# ESP_programmer_QFN.net
KiCad netlist of a schematic drawn in EAGLE
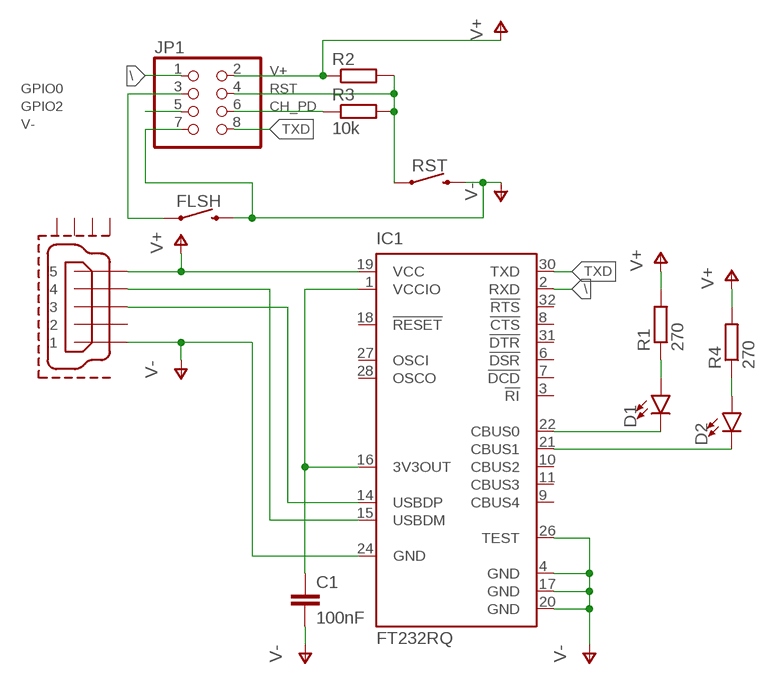
[diagram p0: schematic, sheet 1]

(export (version "E")
  (design (tool "Eeschema 10.0.6"))
  (components
    (comp (ref "C1")
      (value "100nF")
      (footprint "eagle-import:0603")
      (libsource (lib "eagle-import") (part "0.22UF-0603-25V-10%"))
    )
    (comp (ref "D1")
      (value "TX")
      (footprint "eagle-import:LED-0603")
      (libsource (lib "eagle-import") (part "LED-BLUE0603"))
    )
    (comp (ref "D2")
      (value "RX")
      (footprint "eagle-import:LED-0603")
      (libsource (lib "eagle-import") (part "LED-BLUE0603"))
    )
    (comp (ref "FLSH")
      (value "MOMENTARY-SWITCH-SPST-SMD-5.2-REDUNDANT")
      (footprint "eagle-import:TACTILE_SWITCH_SMD_5.2MM")
      (libsource (lib "eagle-import") (part "MOMENTARY-SWITCH-SPST-SMD-5.2-REDUNDANT"))
    )
    (comp (ref "IC1")
      (value "FT232RQ")
      (footprint "eagle-import:QFN32")
      (libsource (lib "eagle-import") (part "FT232RQ"))
    )
    (comp (ref "JP1")
      (value "PINHD-2X4")
      (footprint "eagle-import:2X04")
      (libsource (lib "eagle-import") (part "PINHD-2X4"))
    )
    (comp (ref "R1")
      (value "270")
      (footprint "eagle-import:MINI_MELF-0102R")
      (libsource (lib "eagle-import") (part "R-EU_MELF0102R"))
    )
    (comp (ref "R2")
      (value "10k")
      (footprint "eagle-import:MINI_MELF-0102R")
      (libsource (lib "eagle-import") (part "R-EU_MELF0102R"))
    )
    (comp (ref "R3")
      (value "10k")
      (footprint "eagle-import:MINI_MELF-0102R")
      (libsource (lib "eagle-import") (part "R-EU_MELF0102R"))
    )
    (comp (ref "R4")
      (value "270")
      (footprint "eagle-import:MINI_MELF-0102R")
      (libsource (lib "eagle-import") (part "R-EU_MELF0102R"))
    )
    (comp (ref "RST")
      (value "MOMENTARY-SWITCH-SPST-SMD-5.2-REDUNDANT")
      (footprint "eagle-import:TACTILE_SWITCH_SMD_5.2MM")
      (libsource (lib "eagle-import") (part "MOMENTARY-SWITCH-SPST-SMD-5.2-REDUNDANT"))
    )
    (comp (ref "U1")
      (value "MICRO-USB-RECEPTACLE47589-0001")
      (footprint "eagle-import:47589-0001")
      (libsource (lib "eagle-import") (part "MICRO-USB-RECEPTACLE47589-0001"))
    )
  )
  (nets
    (net (code "1") (name "/CH_PD") (class "Default")
      (node (ref "JP1") (pin "6") (pinfunction "6_6") (pintype "passive"))
      (node (ref "R3") (pin "1") (pinfunction "1_1") (pintype "passive"))
    )
    (net (code "2") (name "/GPIO0") (class "Default")
      (node (ref "FLSH") (pin "1") (pinfunction "1_1") (pintype "passive"))
      (node (ref "FLSH") (pin "2") (pinfunction "1_2") (pintype "passive"))
      (node (ref "JP1") (pin "3") (pinfunction "3_3") (pintype "passive"))
    )
    (net (code "3") (name "/GPIO2") (class "Default")
      (node (ref "JP1") (pin "5") (pinfunction "5_5") (pintype "passive"))
    )
    (net (code "4") (name "/RST") (class "Default")
      (node (ref "JP1") (pin "4") (pinfunction "4_4") (pintype "passive"))
      (node (ref "R2") (pin "2") (pinfunction "2_2") (pintype "passive"))
      (node (ref "R3") (pin "2") (pinfunction "2_2") (pintype "passive"))
      (node (ref "RST") (pin "1") (pinfunction "1_1") (pintype "passive"))
      (node (ref "RST") (pin "2") (pinfunction "1_2") (pintype "passive"))
    )
    (net (code "5") (name "Net-(D1-PadA)") (class "Default")
      (node (ref "D1") (pin "A") (pinfunction "A_A") (pintype "passive"))
      (node (ref "R1") (pin "1") (pinfunction "1_1") (pintype "passive"))
    )
    (net (code "6") (name "Net-(D2-PadA)") (class "Default")
      (node (ref "D2") (pin "A") (pinfunction "A_A") (pintype "passive"))
      (node (ref "R4") (pin "1") (pinfunction "1_1") (pintype "passive"))
    )
    (net (code "7") (name "Net-(IC1-3V3OUT)") (class "Default")
      (node (ref "C1") (pin "1") (pinfunction "1_1") (pintype "passive"))
      (node (ref "IC1") (pin "1") (pinfunction "VCCIO_1") (pintype "power_in"))
      (node (ref "IC1") (pin "16") (pinfunction "3V3OUT_16") (pintype "output"))
    )
    (net (code "8") (name "Net-(IC1-CBUS0)") (class "Default")
      (node (ref "D1") (pin "C") (pinfunction "C_C") (pintype "passive"))
      (node (ref "IC1") (pin "22") (pinfunction "CBUS0_22") (pintype "bidirectional"))
    )
    (net (code "9") (name "Net-(IC1-CBUS1)") (class "Default")
      (node (ref "D2") (pin "C") (pinfunction "C_C") (pintype "passive"))
      (node (ref "IC1") (pin "21") (pinfunction "CBUS1_21") (pintype "bidirectional"))
    )
    (net (code "10") (name "Net-(IC1-USBDM)") (class "Default")
      (node (ref "IC1") (pin "15") (pinfunction "USBDM_15") (pintype "bidirectional"))
      (node (ref "U1") (pin "4") (pinfunction "4_4") (pintype "input"))
    )
    (net (code "11") (name "Net-(IC1-USBDP)") (class "Default")
      (node (ref "IC1") (pin "14") (pinfunction "USBDP_14") (pintype "bidirectional"))
      (node (ref "U1") (pin "3") (pinfunction "3_3") (pintype "input"))
    )
    (net (code "12") (name "TXD") (class "Default")
      (node (ref "IC1") (pin "30") (pinfunction "TXD_30") (pintype "output"))
      (node (ref "JP1") (pin "8") (pinfunction "8_8") (pintype "passive"))
    )
    (net (code "13") (name "V+") (class "Default")
      (node (ref "IC1") (pin "19") (pinfunction "VCC_19") (pintype "power_in"))
      (node (ref "JP1") (pin "2") (pinfunction "2_2") (pintype "passive"))
      (node (ref "R1") (pin "2") (pinfunction "2_2") (pintype "passive"))
      (node (ref "R2") (pin "1") (pinfunction "1_1") (pintype "passive"))
      (node (ref "R4") (pin "2") (pinfunction "2_2") (pintype "passive"))
      (node (ref "U1") (pin "5") (pinfunction "5_5") (pintype "input"))
    )
    (net (code "14") (name "V-") (class "Default")
      (node (ref "C1") (pin "2") (pinfunction "2_2") (pintype "passive"))
      (node (ref "FLSH") (pin "3") (pinfunction "2_3") (pintype "passive"))
      (node (ref "FLSH") (pin "4") (pinfunction "2_4") (pintype "passive"))
      (node (ref "IC1") (pin "17") (pinfunction "GND_17") (pintype "power_in"))
      (node (ref "IC1") (pin "20") (pinfunction "GND_20") (pintype "power_in"))
      (node (ref "IC1") (pin "24") (pinfunction "GND_24") (pintype "power_in"))
      (node (ref "IC1") (pin "26") (pinfunction "TEST_26") (pintype "input"))
      (node (ref "IC1") (pin "4") (pinfunction "GND_4") (pintype "power_in"))
      (node (ref "JP1") (pin "7") (pinfunction "7_7") (pintype "passive"))
      (node (ref "RST") (pin "3") (pinfunction "2_3") (pintype "passive"))
      (node (ref "RST") (pin "4") (pinfunction "2_4") (pintype "passive"))
      (node (ref "U1") (pin "1") (pinfunction "1_1") (pintype "input"))
    )
    (net (code "15") (name "\\") (class "Default")
      (node (ref "IC1") (pin "2") (pinfunction "RXD_2") (pintype "input"))
      (node (ref "JP1") (pin "1") (pinfunction "1_1") (pintype "passive"))
    )
    (net (code "16") (name "unconnected-(IC1-CBUS2-Pad10)") (class "Default")
      (node (ref "IC1") (pin "10") (pinfunction "CBUS2_10") (pintype "bidirectional"))
    )
    (net (code "17") (name "unconnected-(IC1-CBUS3-Pad11)") (class "Default")
      (node (ref "IC1") (pin "11") (pinfunction "CBUS3_11") (pintype "bidirectional"))
    )
    (net (code "18") (name "unconnected-(IC1-CBUS4-Pad9)") (class "Default")
      (node (ref "IC1") (pin "9") (pinfunction "CBUS4_9") (pintype "bidirectional"))
    )
    (net (code "19") (name "unconnected-(IC1-OSCI-Pad27)") (class "Default")
      (node (ref "IC1") (pin "27") (pinfunction "OSCI_27") (pintype "input"))
    )
    (net (code "20") (name "unconnected-(IC1-OSCO-Pad28)") (class "Default")
      (node (ref "IC1") (pin "28") (pinfunction "OSCO_28") (pintype "output"))
    )
    (net (code "21") (name "unconnected-(IC1-~{CTS}-Pad8)") (class "Default")
      (node (ref "IC1") (pin "8") (pinfunction "~{CTS}_8") (pintype "input"))
    )
    (net (code "22") (name "unconnected-(IC1-~{DCD}-Pad7)") (class "Default")
      (node (ref "IC1") (pin "7") (pinfunction "~{DCD}_7") (pintype "input"))
    )
    (net (code "23") (name "unconnected-(IC1-~{DSR}-Pad6)") (class "Default")
      (node (ref "IC1") (pin "6") (pinfunction "~{DSR}_6") (pintype "input"))
    )
    (net (code "24") (name "unconnected-(IC1-~{DTR}-Pad31)") (class "Default")
      (node (ref "IC1") (pin "31") (pinfunction "~{DTR}_31") (pintype "output"))
    )
    (net (code "25") (name "unconnected-(IC1-~{RESET}-Pad18)") (class "Default")
      (node (ref "IC1") (pin "18") (pinfunction "~{RESET}_18") (pintype "input"))
    )
    (net (code "26") (name "unconnected-(IC1-~{RI}-Pad3)") (class "Default")
      (node (ref "IC1") (pin "3") (pinfunction "~{RI}_3") (pintype "input"))
    )
    (net (code "27") (name "unconnected-(IC1-~{RTS}-Pad32)") (class "Default")
      (node (ref "IC1") (pin "32") (pinfunction "~{RTS}_32") (pintype "output"))
    )
    (net (code "28") (name "unconnected-(U1-GND1-PadCASING1)") (class "Default")
      (node (ref "U1") (pin "CASING1") (pinfunction "GND1_CASING1") (pintype "bidirectional"))
    )
    (net (code "29") (name "unconnected-(U1-GND2-PadCASING2)") (class "Default")
      (node (ref "U1") (pin "CASING2") (pinfunction "GND2_CASING2") (pintype "bidirectional"))
    )
    (net (code "30") (name "unconnected-(U1-GND3-PadCASING3)") (class "Default")
      (node (ref "U1") (pin "CASING3") (pinfunction "GND3_CASING3") (pintype "bidirectional"))
    )
    (net (code "31") (name "unconnected-(U1-GND4-PadCASING4)") (class "Default")
      (node (ref "U1") (pin "CASING4") (pinfunction "GND4_CASING4") (pintype "bidirectional"))
    )
    (net (code "32") (name "unconnected-(U1-Pad2)") (class "Default")
      (node (ref "U1") (pin "2") (pinfunction "2_2") (pintype "input"))
    )
  )
)
